# Irrigatron.net
KiCad netlist of a schematic drawn in EasyEDA
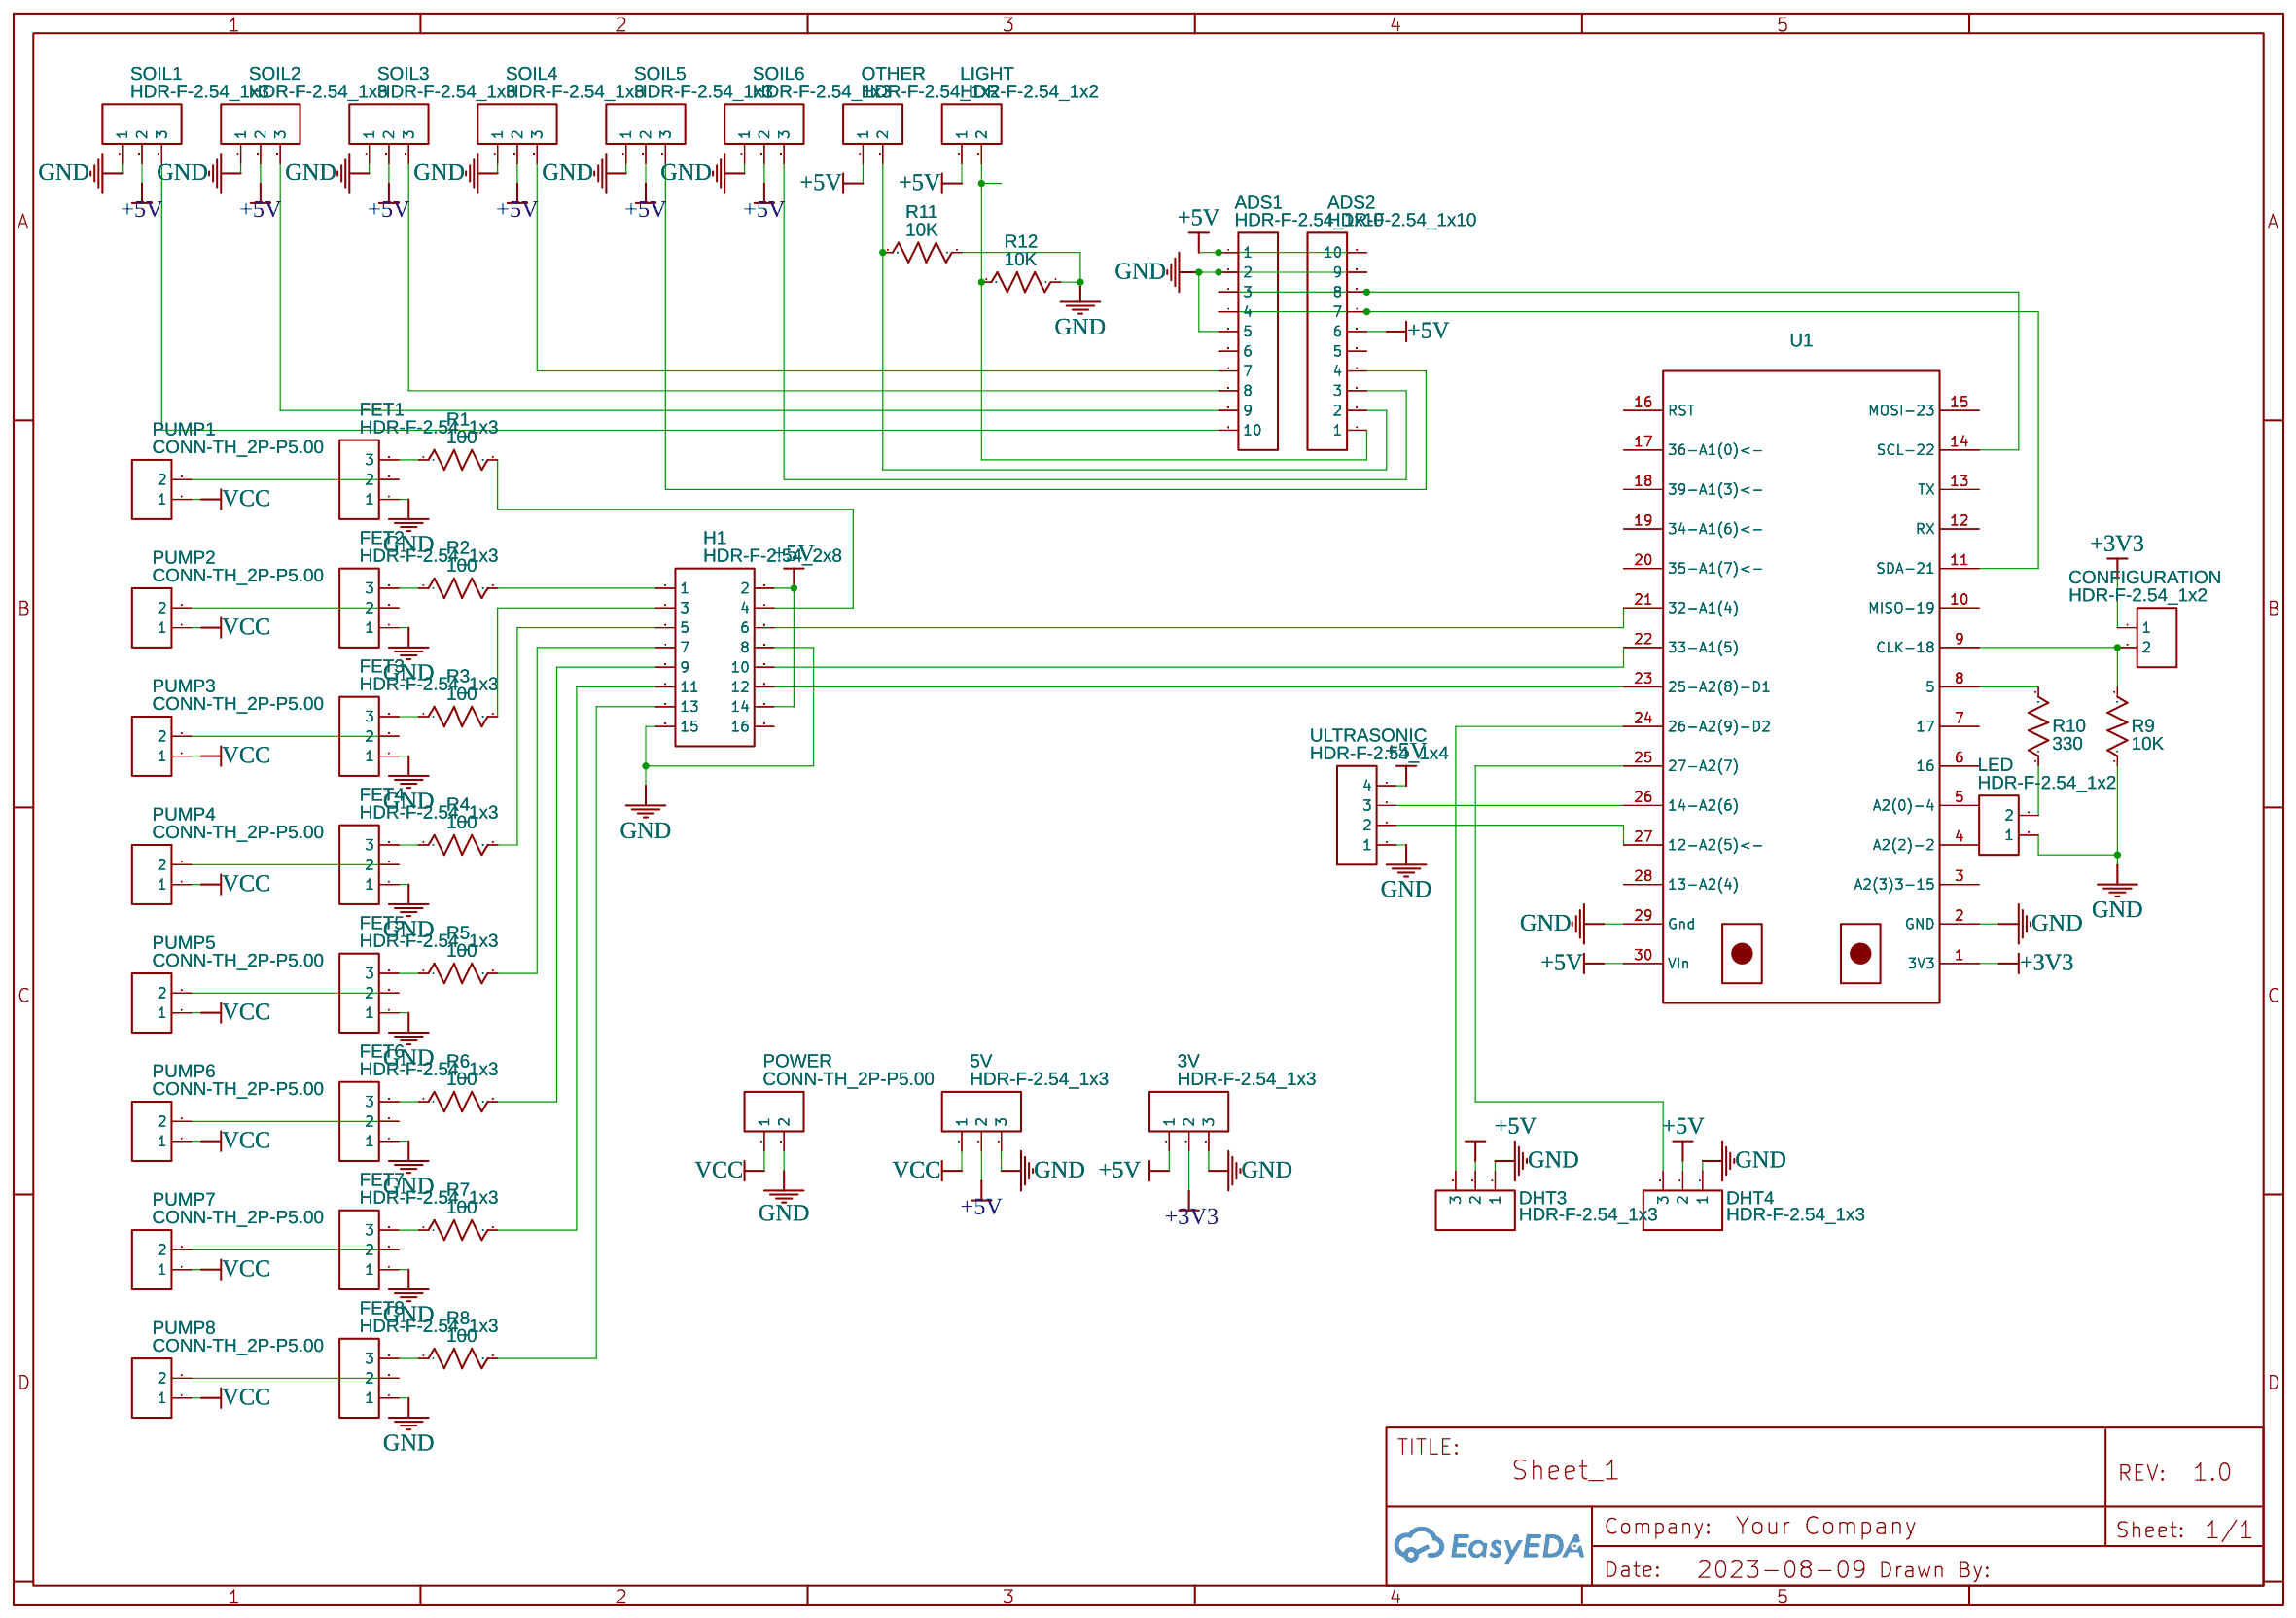
[diagram p0: schematic sheet]

(export (version "E")
  (design (tool "Eeschema 10.0.6"))
  (components
    (comp (ref "3V") (value "HDR-F-2.54_1x3") (libsource (lib "") (part "HDR-F-2.54_1x3_4")))
    (comp (ref "5V") (value "HDR-F-2.54_1x3") (libsource (lib "") (part "HDR-F-2.54_1x3_1")))
    (comp (ref "ADS1") (value "HDR-F-2.54_1x10") (libsource (lib "") (part "HDR-F-2.54_1x10_1")))
    (comp (ref "ADS2") (value "HDR-F-2.54_1x10") (libsource (lib "") (part "HDR-F-2.54_1x10")))
    (comp (ref "CONFIGURATION") (value "HDR-F-2.54_1x2") (libsource (lib "") (part "HDR-F-2.54_1x2_1")))
    (comp (ref "DHT3") (value "HDR-F-2.54_1x3") (libsource (lib "") (part "HDR-F-2.54_1x3_3")))
    (comp (ref "DHT4") (value "HDR-F-2.54_1x3") (libsource (lib "") (part "HDR-F-2.54_1x3_3")))
    (comp (ref "FET1") (value "HDR-F-2.54_1x3") (libsource (lib "") (part "HDR-F-2.54_1x3")))
    (comp (ref "FET2") (value "HDR-F-2.54_1x3") (libsource (lib "") (part "HDR-F-2.54_1x3")))
    (comp (ref "FET3") (value "HDR-F-2.54_1x3") (libsource (lib "") (part "HDR-F-2.54_1x3")))
    (comp (ref "FET4") (value "HDR-F-2.54_1x3") (libsource (lib "") (part "HDR-F-2.54_1x3")))
    (comp (ref "FET5") (value "HDR-F-2.54_1x3") (libsource (lib "") (part "HDR-F-2.54_1x3")))
    (comp (ref "FET6") (value "HDR-F-2.54_1x3") (libsource (lib "") (part "HDR-F-2.54_1x3")))
    (comp (ref "FET7") (value "HDR-F-2.54_1x3") (libsource (lib "") (part "HDR-F-2.54_1x3")))
    (comp (ref "FET8") (value "HDR-F-2.54_1x3") (libsource (lib "") (part "HDR-F-2.54_1x3")))
    (comp (ref "H1") (value "HDR-F-2.54_2x8") (libsource (lib "") (part "HDR-F-2.54_2x8")))
    (comp (ref "LED") (value "HDR-F-2.54_1x2") (libsource (lib "") (part "HDR-F-2.54_1x2_2")))
    (comp (ref "LIGHT") (value "HDR-F-2.54_1x2") (libsource (lib "") (part "HDR-F-2.54_1x2_3")))
    (comp (ref "OTHER") (value "HDR-F-2.54_1x2") (libsource (lib "") (part "HDR-F-2.54_1x2")))
    (comp (ref "POWER") (value "CONN-TH_2P-P5.00") (libsource (lib "") (part "CONN-TH_2P-P5.00_1")))
    (comp (ref "PUMP1") (value "CONN-TH_2P-P5.00") (libsource (lib "") (part "CONN-TH_2P-P5.00")))
    (comp (ref "PUMP2") (value "CONN-TH_2P-P5.00") (libsource (lib "") (part "CONN-TH_2P-P5.00")))
    (comp (ref "PUMP3") (value "CONN-TH_2P-P5.00") (libsource (lib "") (part "CONN-TH_2P-P5.00")))
    (comp (ref "PUMP4") (value "CONN-TH_2P-P5.00") (libsource (lib "") (part "CONN-TH_2P-P5.00")))
    (comp (ref "PUMP5") (value "CONN-TH_2P-P5.00") (libsource (lib "") (part "CONN-TH_2P-P5.00")))
    (comp (ref "PUMP6") (value "CONN-TH_2P-P5.00") (libsource (lib "") (part "CONN-TH_2P-P5.00")))
    (comp (ref "PUMP7") (value "CONN-TH_2P-P5.00") (libsource (lib "") (part "CONN-TH_2P-P5.00")))
    (comp (ref "PUMP8") (value "CONN-TH_2P-P5.00") (libsource (lib "") (part "CONN-TH_2P-P5.00")))
    (comp (ref "R1") (value "100") (libsource (lib "") (part "R_0603_US")))
    (comp (ref "R2") (value "100") (libsource (lib "") (part "R_0603_US")))
    (comp (ref "R3") (value "100") (libsource (lib "") (part "R_0603_US")))
    (comp (ref "R4") (value "100") (libsource (lib "") (part "R_0603_US")))
    (comp (ref "R5") (value "100") (libsource (lib "") (part "R_0603_US")))
    (comp (ref "R6") (value "100") (libsource (lib "") (part "R_0603_US")))
    (comp (ref "R7") (value "100") (libsource (lib "") (part "R_0603_US")))
    (comp (ref "R8") (value "100") (libsource (lib "") (part "R_0603_US")))
    (comp (ref "R9") (value "10K") (libsource (lib "") (part "R_0603_US_1")))
    (comp (ref "R10") (value "330") (libsource (lib "") (part "R_0603_US_1")))
    (comp (ref "R11") (value "10K") (libsource (lib "") (part "R_0603_US_2")))
    (comp (ref "R12") (value "10K") (libsource (lib "") (part "R_0603_US_2")))
    (comp (ref "SOIL1") (value "HDR-F-2.54_1x3") (libsource (lib "") (part "HDR-F-2.54_1x3_2")))
    (comp (ref "SOIL2") (value "HDR-F-2.54_1x3") (libsource (lib "") (part "HDR-F-2.54_1x3_2")))
    (comp (ref "SOIL3") (value "HDR-F-2.54_1x3") (libsource (lib "") (part "HDR-F-2.54_1x3_2")))
    (comp (ref "SOIL4") (value "HDR-F-2.54_1x3") (libsource (lib "") (part "HDR-F-2.54_1x3_2")))
    (comp (ref "SOIL5") (value "HDR-F-2.54_1x3") (libsource (lib "") (part "HDR-F-2.54_1x3_2")))
    (comp (ref "SOIL6") (value "HDR-F-2.54_1x3") (libsource (lib "") (part "HDR-F-2.54_1x3_2")))
    (comp (ref "U1") (value "NO") (libsource (lib "") (part "DOIT ESP32 DEVKIT V1 (30pins)")))
    (comp (ref "ULTRASONIC") (value "HDR-F-2.54_1x4") (libsource (lib "") (part "HDR-F-2.54_1x4")))
  )
  (nets
    (net (code "1") (name "+3V3") (class "Default")
      (node (ref "3V") (pin "2") (pinfunction "2_2") (pintype "input"))
      (node (ref "CONFIGURATION") (pin "1") (pinfunction "1_1") (pintype "input"))
      (node (ref "U1") (pin "1") (pinfunction "3V3_1") (pintype "unspecified"))
    )
    (net (code "2") (name "+5V") (class "Default")
      (node (ref "3V") (pin "1") (pinfunction "1_1") (pintype "input"))
      (node (ref "5V") (pin "2") (pinfunction "2_2") (pintype "input"))
      (node (ref "ADS1") (pin "1") (pinfunction "1_1") (pintype "unspecified"))
      (node (ref "ADS2") (pin "10") (pinfunction "10_10") (pintype "unspecified"))
      (node (ref "ADS2") (pin "6") (pinfunction "6_6") (pintype "unspecified"))
      (node (ref "DHT3") (pin "2") (pinfunction "2_2") (pintype "input"))
      (node (ref "DHT4") (pin "2") (pinfunction "2_2") (pintype "input"))
      (node (ref "H1") (pin "14") (pinfunction "14_14") (pintype "input"))
      (node (ref "H1") (pin "2") (pinfunction "2_2") (pintype "input"))
      (node (ref "LIGHT") (pin "1") (pinfunction "1_1") (pintype "input"))
      (node (ref "OTHER") (pin "1") (pinfunction "1_1") (pintype "input"))
      (node (ref "SOIL1") (pin "2") (pinfunction "2_2") (pintype "input"))
      (node (ref "SOIL2") (pin "2") (pinfunction "2_2") (pintype "input"))
      (node (ref "SOIL3") (pin "2") (pinfunction "2_2") (pintype "input"))
      (node (ref "SOIL4") (pin "2") (pinfunction "2_2") (pintype "input"))
      (node (ref "SOIL5") (pin "2") (pinfunction "2_2") (pintype "input"))
      (node (ref "SOIL6") (pin "2") (pinfunction "2_2") (pintype "input"))
      (node (ref "U1") (pin "30") (pinfunction "VIn_30") (pintype "unspecified"))
      (node (ref "ULTRASONIC") (pin "4") (pinfunction "4_4") (pintype "unspecified"))
    )
    (net (code "3") (name "GND") (class "Default")
      (node (ref "3V") (pin "3") (pinfunction "3_3") (pintype "input"))
      (node (ref "5V") (pin "3") (pinfunction "3_3") (pintype "input"))
      (node (ref "ADS1") (pin "2") (pinfunction "2_2") (pintype "unspecified"))
      (node (ref "ADS1") (pin "5") (pinfunction "5_5") (pintype "unspecified"))
      (node (ref "ADS2") (pin "9") (pinfunction "9_9") (pintype "unspecified"))
      (node (ref "DHT3") (pin "1") (pinfunction "1_1") (pintype "input"))
      (node (ref "DHT4") (pin "1") (pinfunction "1_1") (pintype "input"))
      (node (ref "FET1") (pin "1") (pinfunction "1_1") (pintype "input"))
      (node (ref "FET2") (pin "1") (pinfunction "1_1") (pintype "input"))
      (node (ref "FET3") (pin "1") (pinfunction "1_1") (pintype "input"))
      (node (ref "FET4") (pin "1") (pinfunction "1_1") (pintype "input"))
      (node (ref "FET5") (pin "1") (pinfunction "1_1") (pintype "input"))
      (node (ref "FET6") (pin "1") (pinfunction "1_1") (pintype "input"))
      (node (ref "FET7") (pin "1") (pinfunction "1_1") (pintype "input"))
      (node (ref "FET8") (pin "1") (pinfunction "1_1") (pintype "input"))
      (node (ref "H1") (pin "15") (pinfunction "15_15") (pintype "input"))
      (node (ref "H1") (pin "8") (pinfunction "8_8") (pintype "input"))
      (node (ref "LED") (pin "1") (pinfunction "1_1") (pintype "input"))
      (node (ref "POWER") (pin "2") (pinfunction "2_2") (pintype "unspecified"))
      (node (ref "R11") (pin "1") (pinfunction "1_1") (pintype "unspecified"))
      (node (ref "R12") (pin "1") (pinfunction "1_1") (pintype "unspecified"))
      (node (ref "R9") (pin "1") (pinfunction "1_1") (pintype "unspecified"))
      (node (ref "SOIL1") (pin "1") (pinfunction "1_1") (pintype "input"))
      (node (ref "SOIL2") (pin "1") (pinfunction "1_1") (pintype "input"))
      (node (ref "SOIL3") (pin "1") (pinfunction "1_1") (pintype "input"))
      (node (ref "SOIL4") (pin "1") (pinfunction "1_1") (pintype "input"))
      (node (ref "SOIL5") (pin "1") (pinfunction "1_1") (pintype "input"))
      (node (ref "SOIL6") (pin "1") (pinfunction "1_1") (pintype "input"))
      (node (ref "U1") (pin "2") (pinfunction "GND_2") (pintype "unspecified"))
      (node (ref "U1") (pin "29") (pinfunction "Gnd_29") (pintype "unspecified"))
      (node (ref "ULTRASONIC") (pin "1") (pinfunction "1_1") (pintype "unspecified"))
    )
    (net (code "4") (name "Net-(ADS1-Pad7)") (class "Default")
      (node (ref "ADS1") (pin "7") (pinfunction "7_7") (pintype "unspecified"))
      (node (ref "SOIL4") (pin "3") (pinfunction "3_3") (pintype "input"))
    )
    (net (code "5") (name "Net-(ADS1-Pad8)") (class "Default")
      (node (ref "ADS1") (pin "8") (pinfunction "8_8") (pintype "unspecified"))
      (node (ref "SOIL3") (pin "3") (pinfunction "3_3") (pintype "input"))
    )
    (net (code "6") (name "Net-(ADS1-Pad9)") (class "Default")
      (node (ref "ADS1") (pin "9") (pinfunction "9_9") (pintype "unspecified"))
      (node (ref "SOIL2") (pin "3") (pinfunction "3_3") (pintype "input"))
    )
    (net (code "7") (name "Net-(ADS1-Pad10)") (class "Default")
      (node (ref "ADS1") (pin "10") (pinfunction "10_10") (pintype "unspecified"))
      (node (ref "SOIL1") (pin "3") (pinfunction "3_3") (pintype "input"))
    )
    (net (code "8") (name "Net-(ADS2-Pad1)") (class "Default")
      (node (ref "ADS2") (pin "1") (pinfunction "1_1") (pintype "unspecified"))
      (node (ref "LIGHT") (pin "2") (pinfunction "2_2") (pintype "input"))
      (node (ref "R12") (pin "2") (pinfunction "2_2") (pintype "unspecified"))
    )
    (net (code "9") (name "Net-(ADS2-Pad2)") (class "Default")
      (node (ref "ADS2") (pin "2") (pinfunction "2_2") (pintype "unspecified"))
      (node (ref "OTHER") (pin "2") (pinfunction "2_2") (pintype "input"))
      (node (ref "R11") (pin "2") (pinfunction "2_2") (pintype "unspecified"))
    )
    (net (code "10") (name "Net-(ADS2-Pad3)") (class "Default")
      (node (ref "ADS2") (pin "3") (pinfunction "3_3") (pintype "unspecified"))
      (node (ref "SOIL6") (pin "3") (pinfunction "3_3") (pintype "input"))
    )
    (net (code "11") (name "Net-(ADS2-Pad4)") (class "Default")
      (node (ref "ADS2") (pin "4") (pinfunction "4_4") (pintype "unspecified"))
      (node (ref "SOIL5") (pin "3") (pinfunction "3_3") (pintype "input"))
    )
    (net (code "12") (name "Net-(FET1-Pad2)") (class "Default")
      (node (ref "FET1") (pin "2") (pinfunction "2_2") (pintype "input"))
      (node (ref "PUMP1") (pin "2") (pinfunction "2_2") (pintype "unspecified"))
    )
    (net (code "13") (name "Net-(FET1-Pad3)") (class "Default")
      (node (ref "FET1") (pin "3") (pinfunction "3_3") (pintype "input"))
      (node (ref "R1") (pin "1") (pinfunction "1_1") (pintype "unspecified"))
    )
    (net (code "14") (name "Net-(FET2-Pad2)") (class "Default")
      (node (ref "FET2") (pin "2") (pinfunction "2_2") (pintype "input"))
      (node (ref "PUMP2") (pin "2") (pinfunction "2_2") (pintype "unspecified"))
    )
    (net (code "15") (name "Net-(FET2-Pad3)") (class "Default")
      (node (ref "FET2") (pin "3") (pinfunction "3_3") (pintype "input"))
      (node (ref "R2") (pin "1") (pinfunction "1_1") (pintype "unspecified"))
    )
    (net (code "16") (name "Net-(FET3-Pad2)") (class "Default")
      (node (ref "FET3") (pin "2") (pinfunction "2_2") (pintype "input"))
      (node (ref "PUMP3") (pin "2") (pinfunction "2_2") (pintype "unspecified"))
    )
    (net (code "17") (name "Net-(FET3-Pad3)") (class "Default")
      (node (ref "FET3") (pin "3") (pinfunction "3_3") (pintype "input"))
      (node (ref "R3") (pin "1") (pinfunction "1_1") (pintype "unspecified"))
    )
    (net (code "18") (name "Net-(FET4-Pad2)") (class "Default")
      (node (ref "FET4") (pin "2") (pinfunction "2_2") (pintype "input"))
      (node (ref "PUMP4") (pin "2") (pinfunction "2_2") (pintype "unspecified"))
    )
    (net (code "19") (name "Net-(FET4-Pad3)") (class "Default")
      (node (ref "FET4") (pin "3") (pinfunction "3_3") (pintype "input"))
      (node (ref "R4") (pin "1") (pinfunction "1_1") (pintype "unspecified"))
    )
    (net (code "20") (name "Net-(FET5-Pad2)") (class "Default")
      (node (ref "FET5") (pin "2") (pinfunction "2_2") (pintype "input"))
      (node (ref "PUMP5") (pin "2") (pinfunction "2_2") (pintype "unspecified"))
    )
    (net (code "21") (name "Net-(FET5-Pad3)") (class "Default")
      (node (ref "FET5") (pin "3") (pinfunction "3_3") (pintype "input"))
      (node (ref "R5") (pin "1") (pinfunction "1_1") (pintype "unspecified"))
    )
    (net (code "22") (name "Net-(FET6-Pad2)") (class "Default")
      (node (ref "FET6") (pin "2") (pinfunction "2_2") (pintype "input"))
      (node (ref "PUMP6") (pin "2") (pinfunction "2_2") (pintype "unspecified"))
    )
    (net (code "23") (name "Net-(FET6-Pad3)") (class "Default")
      (node (ref "FET6") (pin "3") (pinfunction "3_3") (pintype "input"))
      (node (ref "R6") (pin "1") (pinfunction "1_1") (pintype "unspecified"))
    )
    (net (code "24") (name "Net-(FET7-Pad2)") (class "Default")
      (node (ref "FET7") (pin "2") (pinfunction "2_2") (pintype "input"))
      (node (ref "PUMP7") (pin "2") (pinfunction "2_2") (pintype "unspecified"))
    )
    (net (code "25") (name "Net-(FET7-Pad3)") (class "Default")
      (node (ref "FET7") (pin "3") (pinfunction "3_3") (pintype "input"))
      (node (ref "R7") (pin "1") (pinfunction "1_1") (pintype "unspecified"))
    )
    (net (code "26") (name "Net-(FET8-Pad2)") (class "Default")
      (node (ref "FET8") (pin "2") (pinfunction "2_2") (pintype "input"))
      (node (ref "PUMP8") (pin "2") (pinfunction "2_2") (pintype "unspecified"))
    )
    (net (code "27") (name "Net-(FET8-Pad3)") (class "Default")
      (node (ref "FET8") (pin "3") (pinfunction "3_3") (pintype "input"))
      (node (ref "R8") (pin "1") (pinfunction "1_1") (pintype "unspecified"))
    )
    (net (code "28") (name "Net-(H1-Pad1)") (class "Default")
      (node (ref "H1") (pin "1") (pinfunction "1_1") (pintype "input"))
      (node (ref "R2") (pin "2") (pinfunction "2_2") (pintype "unspecified"))
    )
    (net (code "29") (name "Net-(H1-Pad3)") (class "Default")
      (node (ref "H1") (pin "3") (pinfunction "3_3") (pintype "input"))
      (node (ref "R3") (pin "2") (pinfunction "2_2") (pintype "unspecified"))
    )
    (net (code "30") (name "Net-(H1-Pad4)") (class "Default")
      (node (ref "H1") (pin "4") (pinfunction "4_4") (pintype "input"))
      (node (ref "R1") (pin "2") (pinfunction "2_2") (pintype "unspecified"))
    )
    (net (code "31") (name "Net-(H1-Pad5)") (class "Default")
      (node (ref "H1") (pin "5") (pinfunction "5_5") (pintype "input"))
      (node (ref "R4") (pin "2") (pinfunction "2_2") (pintype "unspecified"))
    )
    (net (code "32") (name "Net-(H1-Pad7)") (class "Default")
      (node (ref "H1") (pin "7") (pinfunction "7_7") (pintype "input"))
      (node (ref "R5") (pin "2") (pinfunction "2_2") (pintype "unspecified"))
    )
    (net (code "33") (name "Net-(H1-Pad9)") (class "Default")
      (node (ref "H1") (pin "9") (pinfunction "9_9") (pintype "input"))
      (node (ref "R6") (pin "2") (pinfunction "2_2") (pintype "unspecified"))
    )
    (net (code "34") (name "Net-(H1-Pad11)") (class "Default")
      (node (ref "H1") (pin "11") (pinfunction "11_11") (pintype "input"))
      (node (ref "R7") (pin "2") (pinfunction "2_2") (pintype "unspecified"))
    )
    (net (code "35") (name "Net-(H1-Pad13)") (class "Default")
      (node (ref "H1") (pin "13") (pinfunction "13_13") (pintype "input"))
      (node (ref "R8") (pin "2") (pinfunction "2_2") (pintype "unspecified"))
    )
    (net (code "36") (name "Net-(LED-Pad2)") (class "Default")
      (node (ref "LED") (pin "2") (pinfunction "2_2") (pintype "input"))
      (node (ref "R10") (pin "1") (pinfunction "1_1") (pintype "unspecified"))
    )
    (net (code "37") (name "Net-(U1-5)") (class "Default")
      (node (ref "R10") (pin "2") (pinfunction "2_2") (pintype "unspecified"))
      (node (ref "U1") (pin "8") (pinfunction "5_8") (pintype "unspecified"))
    )
    (net (code "38") (name "Net-(U1-12-A2(5)<-)") (class "Default")
      (node (ref "U1") (pin "27") (pinfunction "12-A2(5)<-_27") (pintype "unspecified"))
      (node (ref "ULTRASONIC") (pin "2") (pinfunction "2_2") (pintype "unspecified"))
    )
    (net (code "39") (name "Net-(U1-14-A2(6))") (class "Default")
      (node (ref "U1") (pin "26") (pinfunction "14-A2(6)_26") (pintype "unspecified"))
      (node (ref "ULTRASONIC") (pin "3") (pinfunction "3_3") (pintype "unspecified"))
    )
    (net (code "40") (name "Net-(U1-25-A2(8)-D1)") (class "Default")
      (node (ref "H1") (pin "12") (pinfunction "12_12") (pintype "input"))
      (node (ref "U1") (pin "23") (pinfunction "25-A2(8)-D1_23") (pintype "unspecified"))
    )
    (net (code "41") (name "Net-(U1-26-A2(9)-D2)") (class "Default")
      (node (ref "DHT3") (pin "3") (pinfunction "3_3") (pintype "input"))
      (node (ref "U1") (pin "24") (pinfunction "26-A2(9)-D2_24") (pintype "unspecified"))
    )
    (net (code "42") (name "Net-(U1-27-A2(7))") (class "Default")
      (node (ref "DHT4") (pin "3") (pinfunction "3_3") (pintype "input"))
      (node (ref "U1") (pin "25") (pinfunction "27-A2(7)_25") (pintype "unspecified"))
    )
    (net (code "43") (name "Net-(U1-32-A1(4))") (class "Default")
      (node (ref "H1") (pin "6") (pinfunction "6_6") (pintype "input"))
      (node (ref "U1") (pin "21") (pinfunction "32-A1(4)_21") (pintype "unspecified"))
    )
    (net (code "44") (name "Net-(U1-33-A1(5))") (class "Default")
      (node (ref "H1") (pin "10") (pinfunction "10_10") (pintype "input"))
      (node (ref "U1") (pin "22") (pinfunction "33-A1(5)_22") (pintype "unspecified"))
    )
    (net (code "45") (name "Net-(U1-CLK-18)") (class "Default")
      (node (ref "CONFIGURATION") (pin "2") (pinfunction "2_2") (pintype "input"))
      (node (ref "R9") (pin "2") (pinfunction "2_2") (pintype "unspecified"))
      (node (ref "U1") (pin "9") (pinfunction "CLK-18_9") (pintype "unspecified"))
    )
    (net (code "46") (name "Net-(U1-SCL-22)") (class "Default")
      (node (ref "ADS1") (pin "3") (pinfunction "3_3") (pintype "unspecified"))
      (node (ref "ADS2") (pin "8") (pinfunction "8_8") (pintype "unspecified"))
      (node (ref "U1") (pin "14") (pinfunction "SCL-22_14") (pintype "unspecified"))
    )
    (net (code "47") (name "Net-(U1-SDA-21)") (class "Default")
      (node (ref "ADS1") (pin "4") (pinfunction "4_4") (pintype "unspecified"))
      (node (ref "ADS2") (pin "7") (pinfunction "7_7") (pintype "unspecified"))
      (node (ref "U1") (pin "11") (pinfunction "SDA-21_11") (pintype "unspecified"))
    )
    (net (code "48") (name "VCC") (class "Default")
      (node (ref "5V") (pin "1") (pinfunction "1_1") (pintype "input"))
      (node (ref "POWER") (pin "1") (pinfunction "1_1") (pintype "unspecified"))
      (node (ref "PUMP1") (pin "1") (pinfunction "1_1") (pintype "unspecified"))
      (node (ref "PUMP2") (pin "1") (pinfunction "1_1") (pintype "unspecified"))
      (node (ref "PUMP3") (pin "1") (pinfunction "1_1") (pintype "unspecified"))
      (node (ref "PUMP4") (pin "1") (pinfunction "1_1") (pintype "unspecified"))
      (node (ref "PUMP5") (pin "1") (pinfunction "1_1") (pintype "unspecified"))
      (node (ref "PUMP6") (pin "1") (pinfunction "1_1") (pintype "unspecified"))
      (node (ref "PUMP7") (pin "1") (pinfunction "1_1") (pintype "unspecified"))
      (node (ref "PUMP8") (pin "1") (pinfunction "1_1") (pintype "unspecified"))
    )
    (net (code "49") (name "unconnected-(ADS1-Pad6)") (class "Default")
      (node (ref "ADS1") (pin "6") (pinfunction "6_6") (pintype "unspecified"))
    )
    (net (code "50") (name "unconnected-(ADS2-Pad5)") (class "Default")
      (node (ref "ADS2") (pin "5") (pinfunction "5_5") (pintype "unspecified"))
    )
    (net (code "51") (name "unconnected-(H1-Pad16)") (class "Default")
      (node (ref "H1") (pin "16") (pinfunction "16_16") (pintype "input"))
    )
    (net (code "52") (name "unconnected-(U1-13-A2(4)-Pad28)") (class "Default")
      (node (ref "U1") (pin "28") (pinfunction "13-A2(4)_28") (pintype "unspecified"))
    )
    (net (code "53") (name "unconnected-(U1-16-Pad6)") (class "Default")
      (node (ref "U1") (pin "6") (pinfunction "16_6") (pintype "unspecified"))
    )
    (net (code "54") (name "unconnected-(U1-17-Pad7)") (class "Default")
      (node (ref "U1") (pin "7") (pinfunction "17_7") (pintype "unspecified"))
    )
    (net (code "55") (name "unconnected-(U1-34-A1(6)<--Pad19)") (class "Default")
      (node (ref "U1") (pin "19") (pinfunction "34-A1(6)<-_19") (pintype "unspecified"))
    )
    (net (code "56") (name "unconnected-(U1-35-A1(7)<--Pad20)") (class "Default")
      (node (ref "U1") (pin "20") (pinfunction "35-A1(7)<-_20") (pintype "unspecified"))
    )
    (net (code "57") (name "unconnected-(U1-36-A1(0)<--Pad17)") (class "Default")
      (node (ref "U1") (pin "17") (pinfunction "36-A1(0)<-_17") (pintype "unspecified"))
    )
    (net (code "58") (name "unconnected-(U1-39-A1(3)<--Pad18)") (class "Default")
      (node (ref "U1") (pin "18") (pinfunction "39-A1(3)<-_18") (pintype "unspecified"))
    )
    (net (code "59") (name "unconnected-(U1-A2(0)-4-Pad5)") (class "Default")
      (node (ref "U1") (pin "5") (pinfunction "A2(0)-4_5") (pintype "unspecified"))
    )
    (net (code "60") (name "unconnected-(U1-A2(2)-2-Pad4)") (class "Default")
      (node (ref "U1") (pin "4") (pinfunction "A2(2)-2_4") (pintype "unspecified"))
    )
    (net (code "61") (name "unconnected-(U1-A2(3)3-15-Pad3)") (class "Default")
      (node (ref "U1") (pin "3") (pinfunction "A2(3)3-15_3") (pintype "unspecified"))
    )
    (net (code "62") (name "unconnected-(U1-MISO-19-Pad10)") (class "Default")
      (node (ref "U1") (pin "10") (pinfunction "MISO-19_10") (pintype "unspecified"))
    )
    (net (code "63") (name "unconnected-(U1-MOSI-23-Pad15)") (class "Default")
      (node (ref "U1") (pin "15") (pinfunction "MOSI-23_15") (pintype "unspecified"))
    )
    (net (code "64") (name "unconnected-(U1-RST-Pad16)") (class "Default")
      (node (ref "U1") (pin "16") (pinfunction "RST_16") (pintype "unspecified"))
    )
    (net (code "65") (name "unconnected-(U1-RX-Pad12)") (class "Default")
      (node (ref "U1") (pin "12") (pinfunction "RX_12") (pintype "unspecified"))
    )
    (net (code "66") (name "unconnected-(U1-TX-Pad13)") (class "Default")
      (node (ref "U1") (pin "13") (pinfunction "TX_13") (pintype "unspecified"))
    )
  )
)
